# Micro.net
KiCad netlist of a schematic drawn in Altium Designer
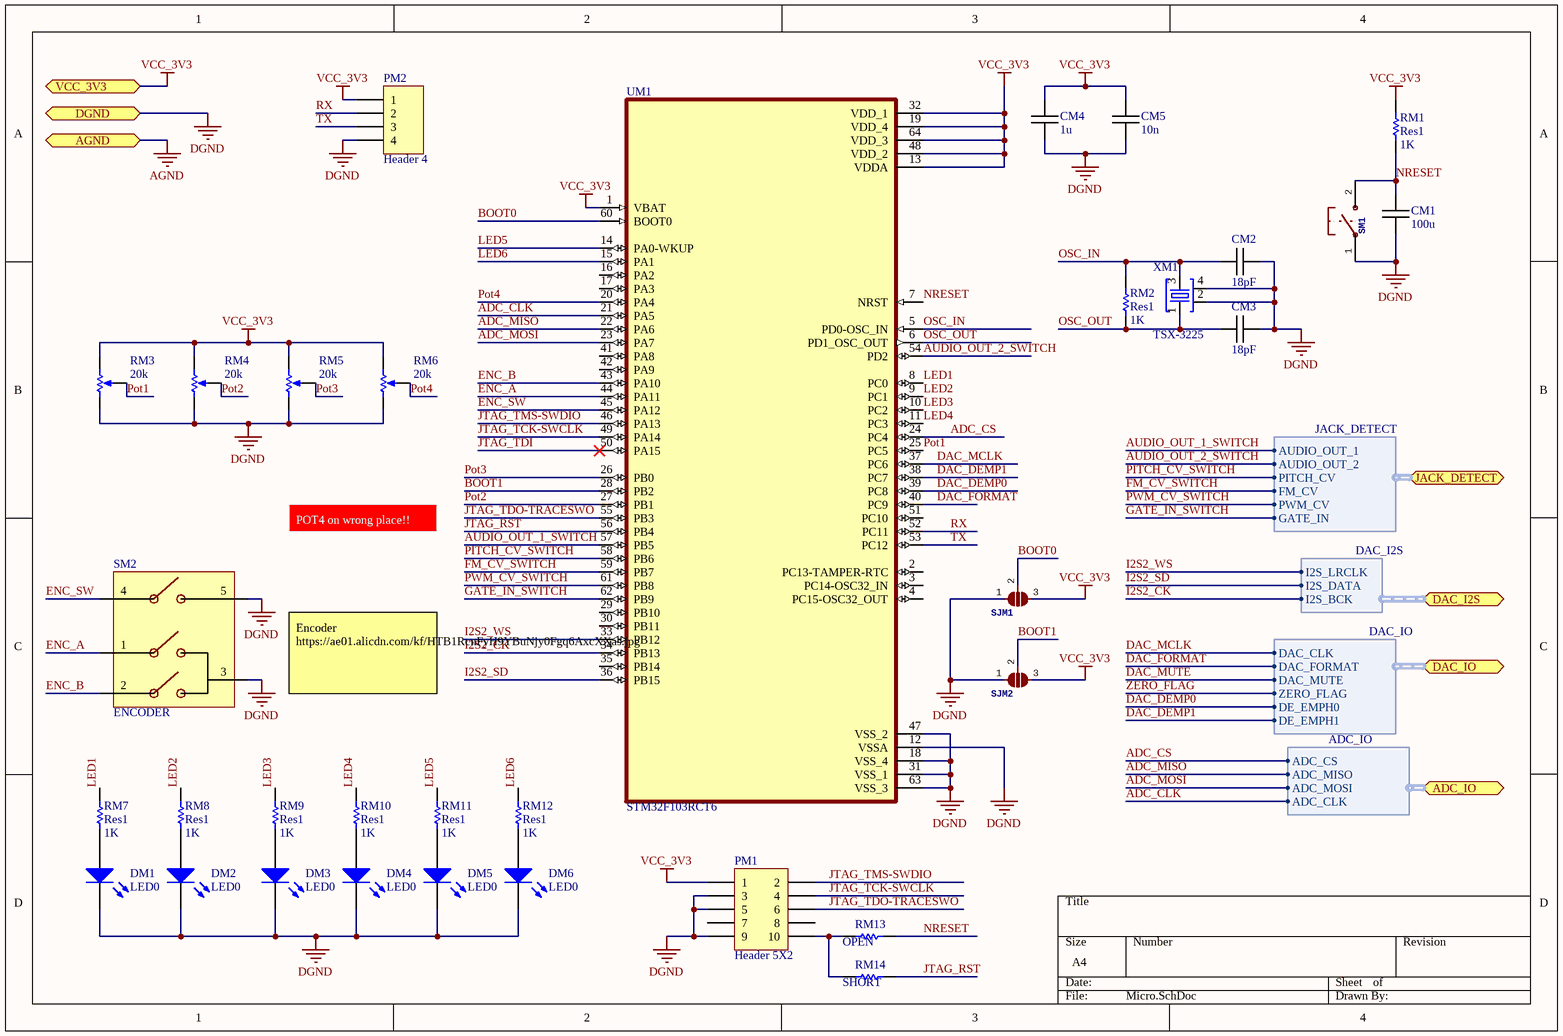
[diagram p0: Micro.SchDoc]

(export (version "E")
  (design (tool "Eeschema 10.0.6"))
  (components
    (comp (ref "CM1")
      (value "100u")
      (footprint "C 0603 / 1608")
      (libsource (lib "Standard") (part "Capacitor"))
    )
    (comp (ref "CM2")
      (value "18pF")
      (footprint "C 0603 / 1608")
      (libsource (lib "Standard") (part "Capacitor"))
    )
    (comp (ref "CM3")
      (value "18pF")
      (footprint "C 0603 / 1608")
      (libsource (lib "Standard") (part "Capacitor"))
    )
    (comp (ref "CM4")
      (value "1u")
      (footprint "C 0603 / 1608")
      (libsource (lib "Standard") (part "Capacitor"))
    )
    (comp (ref "CM5")
      (value "10n")
      (footprint "C 0603 / 1608")
      (libsource (lib "Standard") (part "Capacitor"))
    )
    (comp (ref "DM1")
      (value "LED0")
      (footprint "LED2-2.54-D5.0MM")
      (description "Typical INFRARED GaAs LED")
      (fields (field (name "PUBLISHER") "Altium Limited"))
      (libsource (lib "Miscellaneous Devices") (part "LED0"))
    )
    (comp (ref "DM2")
      (value "LED0")
      (footprint "LED2-2.54-D5.0MM")
      (description "Typical INFRARED GaAs LED")
      (fields (field (name "PUBLISHER") "Altium Limited"))
      (libsource (lib "Miscellaneous Devices") (part "LED0"))
    )
    (comp (ref "DM3")
      (value "LED0")
      (footprint "LED2-2.54-D5.0MM")
      (description "Typical INFRARED GaAs LED")
      (fields (field (name "PUBLISHER") "Altium Limited"))
      (libsource (lib "Miscellaneous Devices") (part "LED0"))
    )
    (comp (ref "DM4")
      (value "LED0")
      (footprint "LED2-2.54-D5.0MM")
      (description "Typical INFRARED GaAs LED")
      (fields (field (name "PUBLISHER") "Altium Limited"))
      (libsource (lib "Miscellaneous Devices") (part "LED0"))
    )
    (comp (ref "DM5")
      (value "LED0")
      (footprint "LED2-2.54-D5.0MM")
      (description "Typical INFRARED GaAs LED")
      (fields (field (name "PUBLISHER") "Altium Limited"))
      (libsource (lib "Miscellaneous Devices") (part "LED0"))
    )
    (comp (ref "DM6")
      (value "LED0")
      (footprint "LED2-2.54-D5.0MM")
      (description "Typical INFRARED GaAs LED")
      (fields (field (name "PUBLISHER") "Altium Limited"))
      (libsource (lib "Miscellaneous Devices") (part "LED0"))
    )
    (comp (ref "PM1")
      (value "Header 5X2")
      (footprint "HDR2X5")
      (description "Header, 5-Pin, Dual row")
      (fields (field (name "PUBLISHER") "Altium Limited"))
      (libsource (lib "Miscellaneous Connectors") (part "Header 5X2"))
    )
    (comp (ref "PM2")
      (value "Header 4")
      (footprint "HDR1X4")
      (description "Header, 4-Pin")
      (fields (field (name "PUBLISHER") "Altium Limited"))
      (libsource (lib "Miscellaneous Connectors") (part "Header 4"))
    )
    (comp (ref "RM1")
      (value "Res1")
      (footprint "RES0603R")
      (description "Resistor")
      (fields (field (name "ALTIUM_VALUE") "1K") (field (name "PUBLISHER") "Altium Limited"))
      (libsource (lib "Standard") (part "Res1"))
    )
    (comp (ref "RM2")
      (value "Res1")
      (footprint "RES0603R")
      (description "Resistor")
      (fields (field (name "ALTIUM_VALUE") "1K") (field (name "PUBLISHER") "Altium Limited"))
      (libsource (lib "Standard") (part "Res1"))
    )
    (comp (ref "RM3")
      (value "20k")
      (footprint "POT-rv09")
      (description "Potentiometer")
      (fields (field (name "PUBLISHER") "Altium Limited"))
      (libsource (lib "Standard") (part "RPot"))
    )
    (comp (ref "RM4")
      (value "20k")
      (footprint "POT-rv09")
      (description "Potentiometer")
      (fields (field (name "PUBLISHER") "Altium Limited"))
      (libsource (lib "Standard") (part "RPot"))
    )
    (comp (ref "RM5")
      (value "20k")
      (footprint "POT-rv09")
      (description "Potentiometer")
      (fields (field (name "PUBLISHER") "Altium Limited"))
      (libsource (lib "Standard") (part "RPot"))
    )
    (comp (ref "RM6")
      (value "20k")
      (footprint "POT-rv09")
      (description "Potentiometer")
      (fields (field (name "PUBLISHER") "Altium Limited"))
      (libsource (lib "Standard") (part "RPot"))
    )
    (comp (ref "RM7")
      (value "Res1")
      (footprint "RES0603R")
      (description "Resistor")
      (fields (field (name "ALTIUM_VALUE") "1K") (field (name "PUBLISHER") "Altium Limited"))
      (libsource (lib "Standard") (part "Res1"))
    )
    (comp (ref "RM8")
      (value "Res1")
      (footprint "RES0603R")
      (description "Resistor")
      (fields (field (name "ALTIUM_VALUE") "1K") (field (name "PUBLISHER") "Altium Limited"))
      (libsource (lib "Standard") (part "Res1"))
    )
    (comp (ref "RM9")
      (value "Res1")
      (footprint "RES0603R")
      (description "Resistor")
      (fields (field (name "ALTIUM_VALUE") "1K") (field (name "PUBLISHER") "Altium Limited"))
      (libsource (lib "Standard") (part "Res1"))
    )
    (comp (ref "RM10")
      (value "Res1")
      (footprint "RES0603R")
      (description "Resistor")
      (fields (field (name "ALTIUM_VALUE") "1K") (field (name "PUBLISHER") "Altium Limited"))
      (libsource (lib "Standard") (part "Res1"))
    )
    (comp (ref "RM11")
      (value "Res1")
      (footprint "RES0603R")
      (description "Resistor")
      (fields (field (name "ALTIUM_VALUE") "1K") (field (name "PUBLISHER") "Altium Limited"))
      (libsource (lib "Standard") (part "Res1"))
    )
    (comp (ref "RM12")
      (value "Res1")
      (footprint "RES0603R")
      (description "Resistor")
      (fields (field (name "ALTIUM_VALUE") "1K") (field (name "PUBLISHER") "Altium Limited"))
      (libsource (lib "Standard") (part "Res1"))
    )
    (comp (ref "RM13")
      (value "OPEN")
      (footprint "RES0603R")
      (description "Resistor")
      (fields (field (name "Comment") "Res1") (field (name "PUBLISHER") "Altium Limited"))
      (libsource (lib "Standard") (part "Res1"))
    )
    (comp (ref "RM14")
      (value "SHORT")
      (footprint "RES0603R")
      (description "Resistor")
      (fields (field (name "Comment") "Res1") (field (name "PUBLISHER") "Altium Limited"))
      (libsource (lib "Standard") (part "Res1"))
    )
    (comp (ref "SJM1")
      (value "2-Way Solder Jumper")
      (footprint "SOLDERJUMPER_2WAY_OPEN_NOPASTE")
      (libsource (lib "Standard2") (part "SOLDERJUMPER_2WAY0603"))
    )
    (comp (ref "SJM2")
      (value "2-Way Solder Jumper")
      (footprint "SOLDERJUMPER_2WAY_OPEN_NOPASTE")
      (libsource (lib "Standard2") (part "SOLDERJUMPER_2WAY0603"))
    )
    (comp (ref "SM1")
      (value "Switch")
      (footprint "PUSH_SMD_3x4")
      (fields (field (name "MANUFACTURER") "Omron") (field (name "MPN") "B3U-1000P"))
      (libsource (lib "Switches") (part "B3U-1000P"))
    )
    (comp (ref "SM2")
      (value "ENCODER")
      (footprint "Rotary Encoder")
      (libsource (lib "Switches") (part "ENCODER"))
    )
    (comp (ref "UM1")
      (value "STM32F103RCT6")
      (footprint "QFP64P1200X1200X160-64N")
      (description "ARMÂ® CortexÂ®-M3 STM32F1 Microcontroller IC 32-Bit 72MHz 256KB _256K x 8_ FLASH")
      (fields (field (name "MF") "STMicroelectronics"))
      (libsource (lib "STM") (part "STM32F103RCT6"))
    )
    (comp (ref "XM1")
      (value "TSX-3225")
      (footprint "TSX-3225")
      (description "16MHz Â±10ppm Crystal 9pF 60 Ohms 4-SMD, No Lead")
      (fields (field (name "MF") "EPSON"))
      (libsource (lib "XTAL") (part "TSX-3225"))
    )
  )
  (nets
    (net (code "5") (name "/ADC_CLK") (class "Default")
      (node (ref "UM1") (pin "21") (pinfunction "PA5_21") (pintype "bidirectional"))
    )
    (net (code "6") (name "/ADC_CS") (class "Default")
      (node (ref "UM1") (pin "24") (pinfunction "PC4_24") (pintype "bidirectional"))
    )
    (net (code "7") (name "/ADC_MISO") (class "Default")
      (node (ref "UM1") (pin "22") (pinfunction "PA6_22") (pintype "bidirectional"))
    )
    (net (code "8") (name "/ADC_MOSI") (class "Default")
      (node (ref "UM1") (pin "23") (pinfunction "PA7_23") (pintype "bidirectional"))
    )
    (net (code "9") (name "/AUDIO_OUT_1_SWITCH") (class "Default")
      (node (ref "UM1") (pin "57") (pinfunction "PB5_57") (pintype "bidirectional"))
    )
    (net (code "10") (name "/AUDIO_OUT_2_SWITCH") (class "Default")
      (node (ref "UM1") (pin "54") (pinfunction "PD2_54") (pintype "bidirectional"))
    )
    (net (code "11") (name "/BOOT0") (class "Default")
      (node (ref "SJM1") (pin "2") (pinfunction "2_2") (pintype "passive"))
      (node (ref "UM1") (pin "60") (pinfunction "BOOT0_60") (pintype "input"))
    )
    (net (code "12") (name "/BOOT1") (class "Default")
      (node (ref "SJM2") (pin "2") (pinfunction "2_2") (pintype "passive"))
      (node (ref "UM1") (pin "28") (pinfunction "PB2_28") (pintype "bidirectional"))
    )
    (net (code "13") (name "/DAC_DEMP0") (class "Default")
      (node (ref "UM1") (pin "39") (pinfunction "PC8_39") (pintype "bidirectional"))
    )
    (net (code "14") (name "/DAC_DEMP1") (class "Default")
      (node (ref "UM1") (pin "38") (pinfunction "PC7_38") (pintype "bidirectional"))
    )
    (net (code "15") (name "/DAC_FORMAT") (class "Default")
      (node (ref "UM1") (pin "40") (pinfunction "PC9_40") (pintype "bidirectional"))
    )
    (net (code "16") (name "/DAC_MCLK") (class "Default")
      (node (ref "UM1") (pin "37") (pinfunction "PC6_37") (pintype "bidirectional"))
    )
    (net (code "18") (name "/ENC_A") (class "Default")
      (node (ref "SM2") (pin "1") (pinfunction "A_1") (pintype "passive"))
      (node (ref "UM1") (pin "44") (pinfunction "PA11_44") (pintype "bidirectional"))
    )
    (net (code "19") (name "/ENC_B") (class "Default")
      (node (ref "SM2") (pin "2") (pinfunction "B_2") (pintype "passive"))
      (node (ref "UM1") (pin "43") (pinfunction "PA10_43") (pintype "bidirectional"))
    )
    (net (code "20") (name "/ENC_SW") (class "Default")
      (node (ref "SM2") (pin "4") (pinfunction "SW_4") (pintype "passive"))
      (node (ref "UM1") (pin "45") (pinfunction "PA12_45") (pintype "bidirectional"))
    )
    (net (code "21") (name "/FM_CV_SWITCH") (class "Default")
      (node (ref "UM1") (pin "59") (pinfunction "PB7_59") (pintype "bidirectional"))
    )
    (net (code "22") (name "/GATE_IN_SWITCH") (class "Default")
      (node (ref "UM1") (pin "62") (pinfunction "PB9_62") (pintype "bidirectional"))
    )
    (net (code "23") (name "/I2S2_CK") (class "Default")
      (node (ref "UM1") (pin "34") (pinfunction "PB13_34") (pintype "bidirectional"))
    )
    (net (code "24") (name "/I2S2_SD") (class "Default")
      (node (ref "UM1") (pin "36") (pinfunction "PB15_36") (pintype "bidirectional"))
    )
    (net (code "25") (name "/I2S2_WS") (class "Default")
      (node (ref "UM1") (pin "33") (pinfunction "PB12_33") (pintype "bidirectional"))
    )
    (net (code "26") (name "/JTAG_RST") (class "Default")
      (node (ref "RM14") (pin "2") (pinfunction "2_2") (pintype "passive"))
      (node (ref "UM1") (pin "56") (pinfunction "PB4_56") (pintype "bidirectional"))
    )
    (net (code "27") (name "/JTAG_TCK-SWCLK") (class "Default")
      (node (ref "PM1") (pin "4") (pinfunction "4_4") (pintype "passive"))
      (node (ref "UM1") (pin "49") (pinfunction "PA14_49") (pintype "bidirectional"))
    )
    (net (code "28") (name "/JTAG_TDI") (class "Default")
      (node (ref "UM1") (pin "50") (pinfunction "PA15_50") (pintype "bidirectional+no_connect"))
    )
    (net (code "29") (name "/JTAG_TDO-TRACESWO") (class "Default")
      (node (ref "PM1") (pin "6") (pinfunction "6_6") (pintype "passive"))
      (node (ref "UM1") (pin "55") (pinfunction "PB3_55") (pintype "bidirectional"))
    )
    (net (code "30") (name "/JTAG_TMS-SWDIO") (class "Default")
      (node (ref "PM1") (pin "2") (pinfunction "2_2") (pintype "passive"))
      (node (ref "UM1") (pin "46") (pinfunction "PA13_46") (pintype "bidirectional"))
    )
    (net (code "31") (name "/LED1") (class "Default")
      (node (ref "RM7") (pin "1") (pinfunction "1_1") (pintype "passive"))
      (node (ref "UM1") (pin "8") (pinfunction "PC0_8") (pintype "bidirectional"))
    )
    (net (code "32") (name "/LED2") (class "Default")
      (node (ref "RM8") (pin "1") (pinfunction "1_1") (pintype "passive"))
      (node (ref "UM1") (pin "9") (pinfunction "PC1_9") (pintype "bidirectional"))
    )
    (net (code "33") (name "/LED3") (class "Default")
      (node (ref "RM9") (pin "1") (pinfunction "1_1") (pintype "passive"))
      (node (ref "UM1") (pin "10") (pinfunction "PC2_10") (pintype "bidirectional"))
    )
    (net (code "34") (name "/LED4") (class "Default")
      (node (ref "RM10") (pin "1") (pinfunction "1_1") (pintype "passive"))
      (node (ref "UM1") (pin "11") (pinfunction "PC3_11") (pintype "bidirectional"))
    )
    (net (code "35") (name "/LED5") (class "Default")
      (node (ref "RM11") (pin "1") (pinfunction "1_1") (pintype "passive"))
      (node (ref "UM1") (pin "14") (pinfunction "PA0-WKUP_14") (pintype "bidirectional"))
    )
    (net (code "36") (name "/LED6") (class "Default")
      (node (ref "RM12") (pin "1") (pinfunction "1_1") (pintype "passive"))
      (node (ref "UM1") (pin "15") (pinfunction "PA1_15") (pintype "bidirectional"))
    )
    (net (code "37") (name "/NRESET") (class "Default")
      (node (ref "CM1") (pin "2") (pinfunction "1_2") (pintype "passive"))
      (node (ref "RM1") (pin "2") (pinfunction "2_2") (pintype "passive"))
      (node (ref "RM13") (pin "2") (pinfunction "2_2") (pintype "passive"))
      (node (ref "SM1") (pin "2") (pinfunction "P$2_2") (pintype "passive"))
      (node (ref "UM1") (pin "7") (pinfunction "NRST_7") (pintype "input"))
    )
    (net (code "38") (name "/OSC_IN") (class "Default")
      (node (ref "CM2") (pin "2") (pinfunction "1_2") (pintype "passive"))
      (node (ref "RM2") (pin "1") (pinfunction "1_1") (pintype "passive"))
      (node (ref "UM1") (pin "5") (pinfunction "PD0-OSC_IN_5") (pintype "input"))
      (node (ref "XM1") (pin "3") (pinfunction "3_3") (pintype "passive"))
    )
    (net (code "39") (name "/OSC_OUT") (class "Default")
      (node (ref "CM3") (pin "2") (pinfunction "1_2") (pintype "passive"))
      (node (ref "RM2") (pin "2") (pinfunction "2_2") (pintype "passive"))
      (node (ref "UM1") (pin "6") (pinfunction "PD1_OSC_OUT_6") (pintype "output"))
      (node (ref "XM1") (pin "1") (pinfunction "1_1") (pintype "passive"))
    )
    (net (code "40") (name "/PITCH_CV_SWITCH") (class "Default")
      (node (ref "UM1") (pin "58") (pinfunction "PB6_58") (pintype "bidirectional"))
    )
    (net (code "41") (name "/PWM_CV_SWITCH") (class "Default")
      (node (ref "UM1") (pin "61") (pinfunction "PB8_61") (pintype "bidirectional"))
    )
    (net (code "42") (name "/Pot1") (class "Default")
      (node (ref "RM3") (pin "3") (pinfunction "TAP_3") (pintype "passive"))
      (node (ref "UM1") (pin "25") (pinfunction "PC5_25") (pintype "bidirectional"))
    )
    (net (code "43") (name "/Pot2") (class "Default")
      (node (ref "RM4") (pin "3") (pinfunction "TAP_3") (pintype "passive"))
      (node (ref "UM1") (pin "27") (pinfunction "PB1_27") (pintype "bidirectional"))
    )
    (net (code "44") (name "/Pot3") (class "Default")
      (node (ref "RM5") (pin "3") (pinfunction "TAP_3") (pintype "passive"))
      (node (ref "UM1") (pin "26") (pinfunction "PB0_26") (pintype "bidirectional"))
    )
    (net (code "45") (name "/Pot4") (class "Default")
      (node (ref "RM6") (pin "3") (pinfunction "TAP_3") (pintype "passive"))
      (node (ref "UM1") (pin "20") (pinfunction "PA4_20") (pintype "bidirectional"))
    )
    (net (code "46") (name "/RX") (class "Default")
      (node (ref "PM2") (pin "2") (pinfunction "2_2") (pintype "passive"))
      (node (ref "UM1") (pin "52") (pinfunction "PC11_52") (pintype "bidirectional"))
    )
    (net (code "47") (name "/TX") (class "Default")
      (node (ref "PM2") (pin "3") (pinfunction "3_3") (pintype "passive"))
      (node (ref "UM1") (pin "53") (pinfunction "PC12_53") (pintype "bidirectional"))
    )
    (net (code "54") (name "DGND") (class "Default")
      (node (ref "CM1") (pin "1") (pinfunction "1_1") (pintype "passive"))
      (node (ref "CM2") (pin "1") (pinfunction "1_1") (pintype "passive"))
      (node (ref "CM3") (pin "1") (pinfunction "1_1") (pintype "passive"))
      (node (ref "CM4") (pin "1") (pinfunction "1_1") (pintype "passive"))
      (node (ref "CM5") (pin "1") (pinfunction "1_1") (pintype "passive"))
      (node (ref "DM1") (pin "2") (pinfunction "K_2") (pintype "passive"))
      (node (ref "DM2") (pin "2") (pinfunction "K_2") (pintype "passive"))
      (node (ref "DM3") (pin "2") (pinfunction "K_2") (pintype "passive"))
      (node (ref "DM4") (pin "2") (pinfunction "K_2") (pintype "passive"))
      (node (ref "DM5") (pin "2") (pinfunction "K_2") (pintype "passive"))
      (node (ref "DM6") (pin "2") (pinfunction "K_2") (pintype "passive"))
      (node (ref "PM1") (pin "3") (pinfunction "3_3") (pintype "passive"))
      (node (ref "PM1") (pin "5") (pinfunction "5_5") (pintype "passive"))
      (node (ref "PM1") (pin "9") (pinfunction "9_9") (pintype "passive"))
      (node (ref "PM2") (pin "4") (pinfunction "4_4") (pintype "passive"))
      (node (ref "RM3") (pin "1") (pinfunction "TOP_1") (pintype "passive"))
      (node (ref "RM4") (pin "1") (pinfunction "TOP_1") (pintype "passive"))
      (node (ref "RM5") (pin "1") (pinfunction "TOP_1") (pintype "passive"))
      (node (ref "RM6") (pin "1") (pinfunction "TOP_1") (pintype "passive"))
      (node (ref "SJM1") (pin "1") (pinfunction "1_1") (pintype "passive"))
      (node (ref "SJM2") (pin "1") (pinfunction "1_1") (pintype "passive"))
      (node (ref "SM1") (pin "1") (pinfunction "P$1_1") (pintype "passive"))
      (node (ref "SM2") (pin "3") (pinfunction "ROT_COMMON_3") (pintype "passive"))
      (node (ref "SM2") (pin "5") (pinfunction "SW_GND_5") (pintype "passive"))
      (node (ref "UM1") (pin "12") (pinfunction "VSSA_12") (pintype "power_in"))
      (node (ref "UM1") (pin "18") (pinfunction "VSS_4_18") (pintype "power_in"))
      (node (ref "UM1") (pin "31") (pinfunction "VSS_1_31") (pintype "power_in"))
      (node (ref "UM1") (pin "47") (pinfunction "VSS_2_47") (pintype "power_in"))
      (node (ref "UM1") (pin "63") (pinfunction "VSS_3_63") (pintype "power_in"))
      (node (ref "XM1") (pin "2") (pinfunction "2_2") (pintype "passive"))
      (node (ref "XM1") (pin "4") (pinfunction "4_4") (pintype "passive"))
    )
    (net (code "55") (name "Net-(DM1-A)") (class "Default")
      (node (ref "DM1") (pin "1") (pinfunction "A_1") (pintype "passive"))
      (node (ref "RM7") (pin "2") (pinfunction "2_2") (pintype "passive"))
    )
    (net (code "56") (name "Net-(DM2-A)") (class "Default")
      (node (ref "DM2") (pin "1") (pinfunction "A_1") (pintype "passive"))
      (node (ref "RM8") (pin "2") (pinfunction "2_2") (pintype "passive"))
    )
    (net (code "57") (name "Net-(DM3-A)") (class "Default")
      (node (ref "DM3") (pin "1") (pinfunction "A_1") (pintype "passive"))
      (node (ref "RM9") (pin "2") (pinfunction "2_2") (pintype "passive"))
    )
    (net (code "58") (name "Net-(DM4-A)") (class "Default")
      (node (ref "DM4") (pin "1") (pinfunction "A_1") (pintype "passive"))
      (node (ref "RM10") (pin "2") (pinfunction "2_2") (pintype "passive"))
    )
    (net (code "59") (name "Net-(DM5-A)") (class "Default")
      (node (ref "DM5") (pin "1") (pinfunction "A_1") (pintype "passive"))
      (node (ref "RM11") (pin "2") (pinfunction "2_2") (pintype "passive"))
    )
    (net (code "60") (name "Net-(DM6-A)") (class "Default")
      (node (ref "DM6") (pin "1") (pinfunction "A_1") (pintype "passive"))
      (node (ref "RM12") (pin "2") (pinfunction "2_2") (pintype "passive"))
    )
    (net (code "61") (name "Net-(PM1-Pad10)") (class "Default")
      (node (ref "PM1") (pin "10") (pinfunction "10_10") (pintype "passive"))
      (node (ref "RM13") (pin "1") (pinfunction "1_1") (pintype "passive"))
      (node (ref "RM14") (pin "1") (pinfunction "1_1") (pintype "passive"))
    )
    (net (code "62") (name "VCC_3V3") (class "Default")
      (node (ref "CM4") (pin "2") (pinfunction "1_2") (pintype "passive"))
      (node (ref "CM5") (pin "2") (pinfunction "1_2") (pintype "passive"))
      (node (ref "PM1") (pin "1") (pinfunction "1_1") (pintype "passive"))
      (node (ref "PM2") (pin "1") (pinfunction "1_1") (pintype "passive"))
      (node (ref "RM1") (pin "1") (pinfunction "1_1") (pintype "passive"))
      (node (ref "RM3") (pin "2") (pinfunction "BOT_2") (pintype "passive"))
      (node (ref "RM4") (pin "2") (pinfunction "BOT_2") (pintype "passive"))
      (node (ref "RM5") (pin "2") (pinfunction "BOT_2") (pintype "passive"))
      (node (ref "RM6") (pin "2") (pinfunction "BOT_2") (pintype "passive"))
      (node (ref "SJM1") (pin "3") (pinfunction "3_3") (pintype "passive"))
      (node (ref "SJM2") (pin "3") (pinfunction "3_3") (pintype "passive"))
      (node (ref "UM1") (pin "1") (pinfunction "VBAT_1") (pintype "input"))
      (node (ref "UM1") (pin "13") (pinfunction "VDDA_13") (pintype "power_in"))
      (node (ref "UM1") (pin "19") (pinfunction "VDD_4_19") (pintype "power_in"))
      (node (ref "UM1") (pin "32") (pinfunction "VDD_1_32") (pintype "power_in"))
      (node (ref "UM1") (pin "48") (pinfunction "VDD_2_48") (pintype "power_in"))
      (node (ref "UM1") (pin "64") (pinfunction "VDD_3_64") (pintype "power_in"))
    )
    (net (code "63") (name "unconnected-(PM1-Pad7)") (class "Default")
      (node (ref "PM1") (pin "7") (pinfunction "7_7") (pintype "passive"))
    )
    (net (code "64") (name "unconnected-(PM1-Pad8)") (class "Default")
      (node (ref "PM1") (pin "8") (pinfunction "8_8") (pintype "passive"))
    )
    (net (code "65") (name "unconnected-(SM2-Pad1)") (class "Default")
      (node (ref "SM2") (pin "1") (pinfunction "1_1") (pintype "passive"))
    )
    (net (code "66") (name "unconnected-(SM2-Pad1)_1") (class "Default")
      (node (ref "SM2") (pin "1") (pinfunction "1_1") (pintype "passive"))
    )
    (net (code "67") (name "unconnected-(SM2-Pad1)_2") (class "Default")
      (node (ref "SM2") (pin "1") (pinfunction "1_1") (pintype "passive"))
    )
    (net (code "68") (name "unconnected-(SM2-Pad2)") (class "Default")
      (node (ref "SM2") (pin "2") (pinfunction "2_2") (pintype "passive"))
    )
    (net (code "69") (name "unconnected-(SM2-Pad2)_1") (class "Default")
      (node (ref "SM2") (pin "2") (pinfunction "2_2") (pintype "passive"))
    )
    (net (code "70") (name "unconnected-(SM2-Pad2)_2") (class "Default")
      (node (ref "SM2") (pin "2") (pinfunction "2_2") (pintype "passive"))
    )
    (net (code "71") (name "unconnected-(UM1-PA2-Pad16)") (class "Default")
      (node (ref "UM1") (pin "16") (pinfunction "PA2_16") (pintype "bidirectional"))
    )
    (net (code "72") (name "unconnected-(UM1-PA3-Pad17)") (class "Default")
      (node (ref "UM1") (pin "17") (pinfunction "PA3_17") (pintype "bidirectional"))
    )
    (net (code "73") (name "unconnected-(UM1-PA8-Pad41)") (class "Default")
      (node (ref "UM1") (pin "41") (pinfunction "PA8_41") (pintype "bidirectional"))
    )
    (net (code "74") (name "unconnected-(UM1-PA9-Pad42)") (class "Default")
      (node (ref "UM1") (pin "42") (pinfunction "PA9_42") (pintype "bidirectional"))
    )
    (net (code "75") (name "unconnected-(UM1-PB10-Pad29)") (class "Default")
      (node (ref "UM1") (pin "29") (pinfunction "PB10_29") (pintype "bidirectional"))
    )
    (net (code "76") (name "unconnected-(UM1-PB11-Pad30)") (class "Default")
      (node (ref "UM1") (pin "30") (pinfunction "PB11_30") (pintype "bidirectional"))
    )
    (net (code "77") (name "unconnected-(UM1-PB14-Pad35)") (class "Default")
      (node (ref "UM1") (pin "35") (pinfunction "PB14_35") (pintype "bidirectional"))
    )
    (net (code "78") (name "unconnected-(UM1-PC10-Pad51)") (class "Default")
      (node (ref "UM1") (pin "51") (pinfunction "PC10_51") (pintype "bidirectional"))
    )
    (net (code "79") (name "unconnected-(UM1-PC13-TAMPER-RTC-Pad2)") (class "Default")
      (node (ref "UM1") (pin "2") (pinfunction "PC13-TAMPER-RTC_2") (pintype "bidirectional"))
    )
    (net (code "80") (name "unconnected-(UM1-PC14-OSC32_IN-Pad3)") (class "Default")
      (node (ref "UM1") (pin "3") (pinfunction "PC14-OSC32_IN_3") (pintype "bidirectional"))
    )
    (net (code "81") (name "unconnected-(UM1-PC15-OSC32_OUT-Pad4)") (class "Default")
      (node (ref "UM1") (pin "4") (pinfunction "PC15-OSC32_OUT_4") (pintype "bidirectional"))
    )
  )
)
